# Supply.net
KiCad netlist of a schematic drawn in Altium Designer
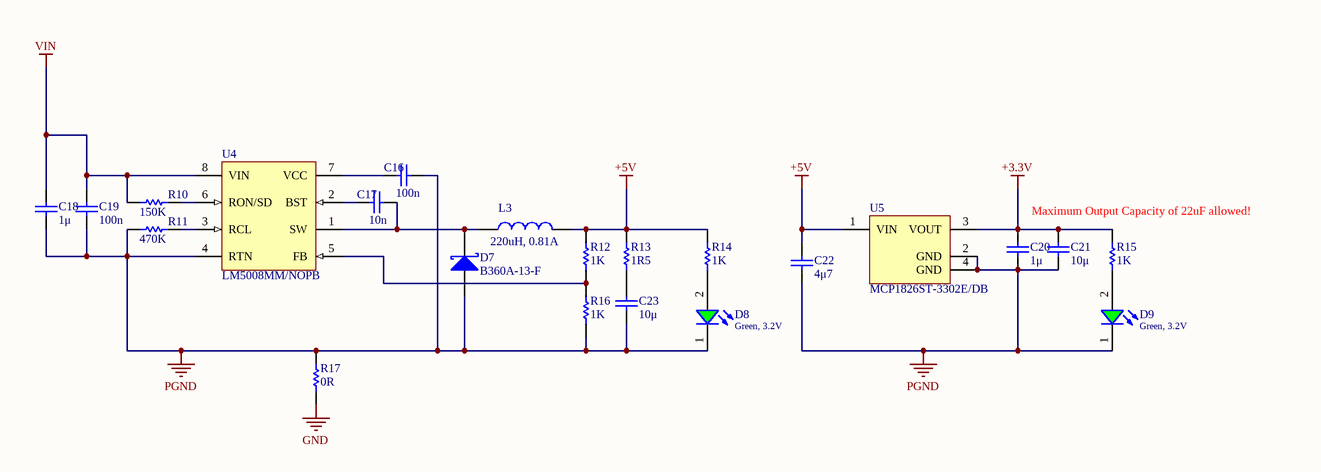
[diagram p0: Supply.SchDoc]

(export (version "E")
  (design (tool "Eeschema 10.0.6"))
  (components
    (comp (ref "C16")
      (value "100n")
      (footprint "CAPC0603(1608)55_N")
      (description "Keramikvielschichtkondensator, SMD, Baureihe MC, ± 10%")
      (fields (field (name "MANUFACTURER") "TDK") (field (name "TOLERANCE") "± 10%"))
      (libsource (lib "Res&Caps") (part "Cap 100n"))
    )
    (comp (ref "C17")
      (value "10n")
      (footprint "CAPC0603(1608)55_N")
      (description "Keramikvielschichtkondensator, SMD, Baureihe MC, ± 10%")
      (fields (field (name "MANUFACTURER") "TDK") (field (name "TOLERANCE") "± 10%"))
      (libsource (lib "Res&Caps") (part "Cap 10n"))
    )
    (comp (ref "C18")
      (value "1μ")
      (footprint "CAPC0603(1608)55_N")
      (description "Keramikvielschichtkondensator, SMD, Baureihe MC, ± 10%")
      (fields (field (name "MANUFACTURER") "TDK") (field (name "TOLERANCE") "± 10%"))
      (libsource (lib "Res&Caps") (part "Cap 1μ"))
    )
    (comp (ref "C19")
      (value "100n")
      (footprint "CAPC0603(1608)55_N")
      (description "Keramikvielschichtkondensator, SMD, Baureihe MC, ± 10%")
      (fields (field (name "MANUFACTURER") "TDK") (field (name "TOLERANCE") "± 10%"))
      (libsource (lib "Res&Caps") (part "Cap 100n"))
    )
    (comp (ref "C20")
      (value "1μ")
      (footprint "CAPC0603(1608)55_N")
      (description "Keramikvielschichtkondensator, SMD, Baureihe MC, ± 10%")
      (fields (field (name "MANUFACTURER") "TDK") (field (name "TOLERANCE") "± 10%"))
      (libsource (lib "Res&Caps") (part "Cap 1μ"))
    )
    (comp (ref "C21")
      (value "10μ")
      (footprint "CAPC0603(1608)55_N")
      (description "Keramikvielschichtkondensator, SMD, Baureihe MC, ± 10%")
      (fields (field (name "MANUFACTURER") "TDK") (field (name "TOLERANCE") "± 10%"))
      (libsource (lib "Res&Caps") (part "Cap 10μ"))
    )
    (comp (ref "C22")
      (value "4μ7")
      (footprint "CAPC0603(1608)55_N")
      (description "Keramikvielschichtkondensator, SMD, Baureihe MC, ± 10%")
      (fields (field (name "MANUFACTURER") "TDK") (field (name "TOLERANCE") "± 10%"))
      (libsource (lib "Res&Caps") (part "Cap 4μ7"))
    )
    (comp (ref "C23")
      (value "10μ")
      (footprint "CAPC0603(1608)55_N")
      (description "Keramikvielschichtkondensator, SMD, Baureihe MC, ± 10%")
      (fields (field (name "MANUFACTURER") "TDK") (field (name "TOLERANCE") "± 10%"))
      (libsource (lib "Res&Caps") (part "Cap 10μ"))
    )
    (comp (ref "D7")
      (value "B360A-13-F")
      (footprint "DIOD-B360A_V")
      (description "Schottky Barrier Rectifier, 3 A, -55 to 150 degC, 2-Pin Molded, RoHS, Tape and Reel")
      (fields (field (name "MANUFACTURER") "DiodesIncorporated"))
      (libsource (lib "Altium Content Vault") (part "DSKY-AK-2"))
    )
    (comp (ref "D8")
      (value "Green, 3.2V")
      (footprint "WL-SMCW_0603_H=0.25mm")
      (description "WL-SMCW SMT Mono-color Chip LED Waterclear, size 0603, Green, 3.2V, 140deg")
      (fields (field (name "PART NUMBER") "150060GS75020") (field (name "PUBLISHER") "Wurth Elektronik"))
      (libsource (lib "LEDs") (part "150060GS75020"))
    )
    (comp (ref "D9")
      (value "Green, 3.2V")
      (footprint "WL-SMCW_0603_H=0.25mm")
      (description "WL-SMCW SMT Mono-color Chip LED Waterclear, size 0603, Green, 3.2V, 140deg")
      (fields (field (name "PART NUMBER") "150060GS75020") (field (name "PUBLISHER") "Wurth Elektronik"))
      (libsource (lib "LEDs") (part "150060GS75020"))
    )
    (comp (ref "L3")
      (value "220uH, 0.81A")
      (footprint "WE-LQS_8040")
      (description "WE-LQS SMT Power Inductor, size 8040, 220uH, 0.81A")
      (fields
        (field (name "MANUFACTURER") "Wurth Elektronik")
        (field (name "MANUFACTURER PART NUMBER") "74404084221")
      )
      (libsource (lib "*") (part "74404084221"))
    )
    (comp (ref "R10")
      (value "150K")
      (footprint "RESC0603(1608)_N")
      (description "Chipwiderstand, SMD, Baureihe MC, 1%")
      (fields (field (name "MANUFACTURER") "Multicomp") (field (name "POWER") "100mW"))
      (libsource (lib "Res&Caps") (part "Res 150K"))
    )
    (comp (ref "R11")
      (value "470K")
      (footprint "RESC0603(1608)_N")
      (description "Chipwiderstand, SMD, Baureihe MC, 1%")
      (fields (field (name "MANUFACTURER") "Multicomp") (field (name "POWER") "100mW"))
      (libsource (lib "Res&Caps") (part "Res 470K"))
    )
    (comp (ref "R12")
      (value "1K")
      (footprint "RESC0603(1608)_N")
      (description "Chipwiderstand, SMD, Baureihe MC, 1%")
      (fields (field (name "MANUFACTURER") "Multicomp") (field (name "POWER") "100mW"))
      (libsource (lib "Res&Caps") (part "Res 1K"))
    )
    (comp (ref "R13")
      (value "1R5")
      (footprint "RESC0603(1608)_N")
      (description "Chipwiderstand, SMD, Baureihe MC, 1%")
      (fields (field (name "MANUFACTURER") "Multicomp") (field (name "POWER") "100mW"))
      (libsource (lib "Res&Caps") (part "Res 1R5"))
    )
    (comp (ref "R14")
      (value "1K")
      (footprint "RESC0603(1608)_N")
      (description "Chipwiderstand, SMD, Baureihe MC, 1%")
      (fields (field (name "MANUFACTURER") "Multicomp") (field (name "POWER") "100mW"))
      (libsource (lib "Res&Caps") (part "Res 1K"))
    )
    (comp (ref "R15")
      (value "1K")
      (footprint "RESC0603(1608)_N")
      (description "Chipwiderstand, SMD, Baureihe MC, 1%")
      (fields (field (name "MANUFACTURER") "Multicomp") (field (name "POWER") "100mW"))
      (libsource (lib "Res&Caps") (part "Res 1K"))
    )
    (comp (ref "R16")
      (value "1K")
      (footprint "RESC0603(1608)_N")
      (description "Chipwiderstand, SMD, Baureihe MC, 1%")
      (fields (field (name "MANUFACTURER") "Multicomp") (field (name "POWER") "100mW"))
      (libsource (lib "Res&Caps") (part "Res 1K"))
    )
    (comp (ref "R17")
      (value "0R")
      (footprint "RESC0603(1608)_N")
      (description "Chipwiderstand, SMD, Baureihe MC, 1%")
      (fields (field (name "MANUFACTURER") "Multicomp") (field (name "POWER") "100mW"))
      (libsource (lib "Res&Caps") (part "Res 0R"))
    )
    (comp (ref "U4")
      (value "LM5008MM/NOPB")
      (footprint "DGK0008A_M")
      (description "High Voltage (100V) Step Down Switching Regulator, 8-pin MSOP, Pb-Free")
      (fields (field (name "MANUFACTURER") "Texas Instruments"))
      (libsource (lib "Altium Content Vault") (part "PM-SWREG-LM5008-8"))
    )
    (comp (ref "U5")
      (value "MCP1826ST-3302E/DB")
      (footprint "SOT-223-DB3_M")
      (libsource (lib "Altium Content Vault") (part "PM-LINEREG-MCP1826-IL4"))
    )
  )
  (nets
    (net (code "1") (name "+3.3V") (class "Default")
      (node (ref "C20") (pin "2") (pinfunction "2_2") (pintype "passive"))
      (node (ref "C21") (pin "2") (pinfunction "2_2") (pintype "passive"))
      (node (ref "R15") (pin "2") (pinfunction "2_2") (pintype "passive"))
      (node (ref "U5") (pin "3") (pinfunction "VOUT_3") (pintype "power_in"))
    )
    (net (code "2") (name "+5V") (class "Default")
      (node (ref "C22") (pin "2") (pinfunction "2_2") (pintype "passive"))
      (node (ref "L3") (pin "2") (pinfunction "2_2") (pintype "passive"))
      (node (ref "R12") (pin "2") (pinfunction "2_2") (pintype "passive"))
      (node (ref "R13") (pin "2") (pinfunction "2_2") (pintype "passive"))
      (node (ref "R14") (pin "2") (pinfunction "2_2") (pintype "passive"))
      (node (ref "U5") (pin "1") (pinfunction "VIN_1") (pintype "power_in"))
    )
    (net (code "3") (name "GND") (class "Default")
      (node (ref "R17") (pin "1") (pinfunction "1_1") (pintype "passive"))
    )
    (net (code "4") (name "Net-(C23-Pad2)") (class "Default")
      (node (ref "C23") (pin "2") (pinfunction "2_2") (pintype "passive"))
      (node (ref "R13") (pin "1") (pinfunction "1_1") (pintype "passive"))
    )
    (net (code "5") (name "Net-(D7-K)") (class "Default")
      (node (ref "C17") (pin "2") (pinfunction "2_2") (pintype "passive"))
      (node (ref "D7") (pin "2") (pinfunction "K_2") (pintype "passive"))
      (node (ref "L3") (pin "1") (pinfunction "1_1") (pintype "passive"))
      (node (ref "U4") (pin "1") (pinfunction "SW_1") (pintype "power_in"))
    )
    (net (code "6") (name "Net-(D8-A)") (class "Default")
      (node (ref "D8") (pin "2") (pinfunction "A_2") (pintype "passive"))
      (node (ref "R14") (pin "1") (pinfunction "1_1") (pintype "passive"))
    )
    (net (code "7") (name "Net-(D9-A)") (class "Default")
      (node (ref "D9") (pin "2") (pinfunction "A_2") (pintype "passive"))
      (node (ref "R15") (pin "1") (pinfunction "1_1") (pintype "passive"))
    )
    (net (code "8") (name "Net-(U4-BST)") (class "Default")
      (node (ref "C17") (pin "1") (pinfunction "1_1") (pintype "passive"))
      (node (ref "U4") (pin "2") (pinfunction "BST_2") (pintype "input"))
    )
    (net (code "9") (name "Net-(U4-FB)") (class "Default")
      (node (ref "R12") (pin "1") (pinfunction "1_1") (pintype "passive"))
      (node (ref "R16") (pin "2") (pinfunction "2_2") (pintype "passive"))
      (node (ref "U4") (pin "5") (pinfunction "FB_5") (pintype "input"))
    )
    (net (code "10") (name "Net-(U4-RCL)") (class "Default")
      (node (ref "R11") (pin "2") (pinfunction "2_2") (pintype "passive"))
      (node (ref "U4") (pin "3") (pinfunction "RCL_3") (pintype "input"))
    )
    (net (code "11") (name "Net-(U4-RON{slash}SD)") (class "Default")
      (node (ref "R10") (pin "2") (pinfunction "2_2") (pintype "passive"))
      (node (ref "U4") (pin "6") (pinfunction "RON/SD_6") (pintype "input"))
    )
    (net (code "12") (name "Net-(U4-VCC)") (class "Default")
      (node (ref "C16") (pin "2") (pinfunction "2_2") (pintype "passive"))
      (node (ref "U4") (pin "7") (pinfunction "VCC_7") (pintype "power_in"))
    )
    (net (code "13") (name "PGND") (class "Default")
      (node (ref "C16") (pin "1") (pinfunction "1_1") (pintype "passive"))
      (node (ref "C18") (pin "1") (pinfunction "1_1") (pintype "passive"))
      (node (ref "C19") (pin "1") (pinfunction "1_1") (pintype "passive"))
      (node (ref "C20") (pin "1") (pinfunction "1_1") (pintype "passive"))
      (node (ref "C21") (pin "1") (pinfunction "1_1") (pintype "passive"))
      (node (ref "C22") (pin "1") (pinfunction "1_1") (pintype "passive"))
      (node (ref "C23") (pin "1") (pinfunction "1_1") (pintype "passive"))
      (node (ref "D7") (pin "1") (pinfunction "A_1") (pintype "passive"))
      (node (ref "D8") (pin "1") (pinfunction "K_1") (pintype "passive"))
      (node (ref "D9") (pin "1") (pinfunction "K_1") (pintype "passive"))
      (node (ref "R11") (pin "1") (pinfunction "1_1") (pintype "passive"))
      (node (ref "R16") (pin "1") (pinfunction "1_1") (pintype "passive"))
      (node (ref "R17") (pin "2") (pinfunction "2_2") (pintype "passive"))
      (node (ref "U4") (pin "4") (pinfunction "RTN_4") (pintype "power_in"))
      (node (ref "U5") (pin "2") (pinfunction "GND_2") (pintype "power_in"))
      (node (ref "U5") (pin "4") (pinfunction "GND_4") (pintype "power_in"))
    )
    (net (code "14") (name "VIN") (class "Default")
      (node (ref "C18") (pin "2") (pinfunction "2_2") (pintype "passive"))
      (node (ref "C19") (pin "2") (pinfunction "2_2") (pintype "passive"))
      (node (ref "R10") (pin "1") (pinfunction "1_1") (pintype "passive"))
      (node (ref "U4") (pin "8") (pinfunction "VIN_8") (pintype "power_in"))
    )
  )
)
